# SPI_Control.net
KiCad netlist of a schematic drawn in Altium Designer
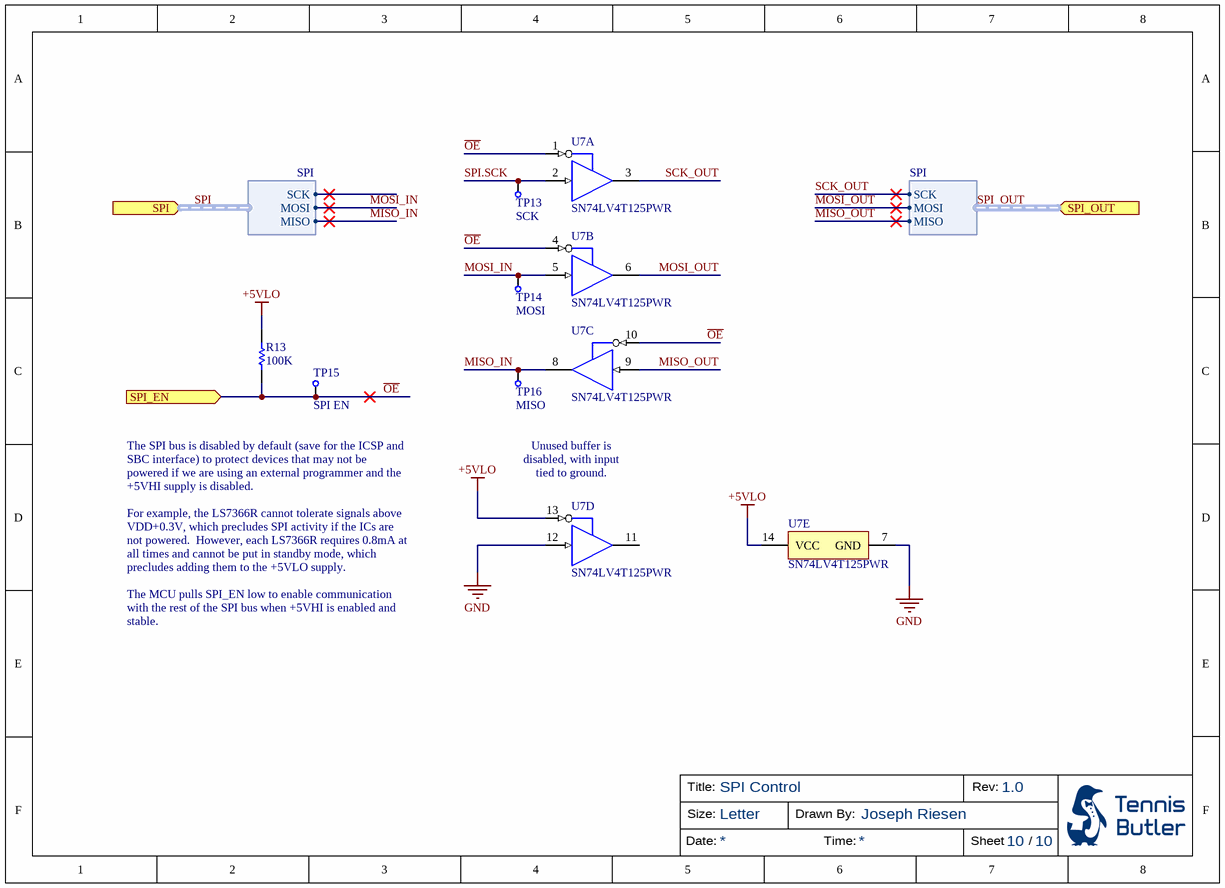
[diagram p0: SPI Control.SchDoc]

(export (version "E")
  (design (tool "Eeschema 10.0.6"))
  (components
    (comp (ref "R13")
      (value "100K")
      (footprint "RESC2013X70X40ML20T20")
      (description "RES SMD 100K OHM 1% 1/8W 0805")
      (fields (field (name "PART NUMBER") "ERJ-6ENF1003V") (field (name "MANUFACTURER") "Panasonic"))
      (libsource (lib "Altium Content Vault") (part "RES"))
    )
    (comp (ref "TP13")
      (value "SCK")
      (footprint "Test Point")
      (libsource (lib "Miscellaneous") (part "Test Point"))
    )
    (comp (ref "TP14")
      (value "MOSI")
      (footprint "Test Point")
      (libsource (lib "Miscellaneous") (part "Test Point"))
    )
    (comp (ref "TP15")
      (value "SPI EN")
      (footprint "Test Point")
      (libsource (lib "Miscellaneous") (part "Test Point"))
    )
    (comp (ref "TP16")
      (value "MISO")
      (footprint "Test Point")
      (libsource (lib "Miscellaneous") (part "Test Point"))
    )
    (comp (ref "U7")
      (value "SN74LV4T125PWR")
      (footprint "TSOP65P640X120-14M")
      (fields (field (name "MANUFACTURER") "Texas Instruments"))
      (libsource (lib "SN74LV4T125") (part "SN74LV4T125PWR"))
    )
  )
  (nets
    (net (code "3") (name "+5VLO") (class "Default")
      (node (ref "R13") (pin "2") (pinfunction "2_2") (pintype "passive"))
      (node (ref "U7") (pin "13") (pinfunction "4~{OE}_13") (pintype "input"))
      (node (ref "U7") (pin "14") (pinfunction "VCC_14") (pintype "power_in"))
    )
    (net (code "4") (name "/MISO_IN") (class "Default")
      (node (ref "TP16") (pin "1") (pinfunction "1_1") (pintype "passive"))
      (node (ref "U7") (pin "8") (pinfunction "3Y_8") (pintype "tri_state"))
    )
    (net (code "5") (name "/MISO_OUT") (class "Default")
      (node (ref "U7") (pin "9") (pinfunction "3A_9") (pintype "input"))
    )
    (net (code "6") (name "/MOSI_IN") (class "Default")
      (node (ref "TP14") (pin "1") (pinfunction "1_1") (pintype "passive"))
      (node (ref "U7") (pin "5") (pinfunction "2A_5") (pintype "input"))
    )
    (net (code "7") (name "/MOSI_OUT") (class "Default")
      (node (ref "U7") (pin "6") (pinfunction "2Y_6") (pintype "tri_state"))
    )
    (net (code "8") (name "/SCK_OUT") (class "Default")
      (node (ref "U7") (pin "3") (pinfunction "1Y_3") (pintype "tri_state"))
    )
    (net (code "9") (name "/SPI.SCK") (class "Default")
      (node (ref "TP13") (pin "1") (pinfunction "1_1") (pintype "passive"))
      (node (ref "U7") (pin "2") (pinfunction "1A_2") (pintype "input"))
    )
    (net (code "12") (name "/~{OE}") (class "Default")
      (node (ref "R13") (pin "1") (pinfunction "1_1") (pintype "passive"))
      (node (ref "TP15") (pin "1") (pinfunction "1_1") (pintype "passive"))
      (node (ref "U7") (pin "1") (pinfunction "1~{OE}_1") (pintype "input"))
      (node (ref "U7") (pin "10") (pinfunction "3~{OE}_10") (pintype "input"))
      (node (ref "U7") (pin "4") (pinfunction "2~{OE}_4") (pintype "input"))
    )
    (net (code "13") (name "GND") (class "Default")
      (node (ref "U7") (pin "12") (pinfunction "4A_12") (pintype "input"))
      (node (ref "U7") (pin "7") (pinfunction "GND_7") (pintype "power_in"))
    )
    (net (code "14") (name "unconnected-(U7D-4Y-Pad11)") (class "Default")
      (node (ref "U7") (pin "11") (pinfunction "4Y_11") (pintype "tri_state"))
    )
  )
)
